# power_supply.net
KiCad netlist of a schematic drawn in Altium Designer
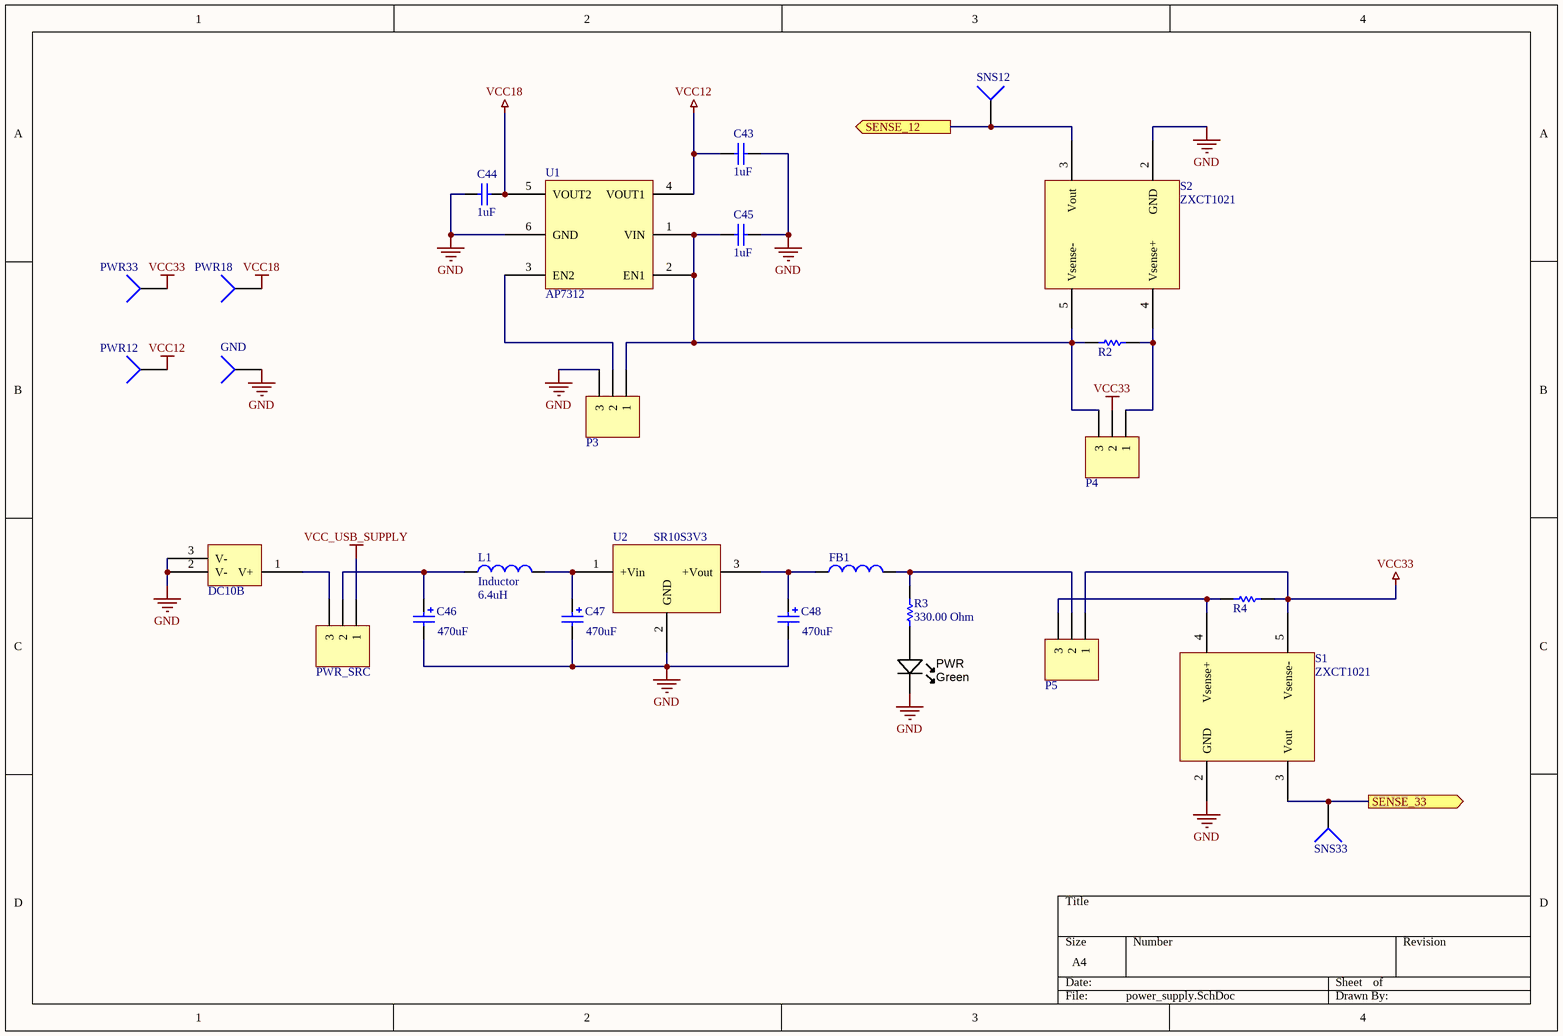
[diagram p0: power_supply.SchDoc]

(export (version "E")
  (design (tool "Eeschema 10.0.6"))
  (components
    (comp (ref "C43")
      (value "1uF")
      (footprint "CAPC0805(2012)100_N")
      (description "CAP 1uF 16V ±10% 0805 (2012 Metric) Thickness 1mm SMD")
      (fields (field (name "TOLERANCE") "±10%"))
      (libsource (lib "Altium Content Vault") (part "CMP-1036-04747-1"))
    )
    (comp (ref "C44")
      (value "1uF")
      (footprint "CAPC0805(2012)100_N")
      (description "CAP 1uF 16V ±10% 0805 (2012 Metric) Thickness 1mm SMD")
      (fields (field (name "TOLERANCE") "±10%"))
      (libsource (lib "Altium Content Vault") (part "CMP-1036-04747-1"))
    )
    (comp (ref "C45")
      (value "1uF")
      (footprint "CAPC0805(2012)100_N")
      (description "CAP 1uF 16V ±10% 0805 (2012 Metric) Thickness 1mm SMD")
      (fields (field (name "TOLERANCE") "±10%"))
      (libsource (lib "Altium Content Vault") (part "CMP-1036-04747-1"))
    )
    (comp (ref "C46")
      (value "470uF")
      (footprint "CAP470uF")
      (description "Polarized Capacitor (Axial)")
      (fields (field (name "Comment") "Cap Pol2") (field (name "PUBLISHER") "Altium Limited"))
      (libsource (lib "Miscellaneous Devices") (part "Cap Pol2"))
    )
    (comp (ref "C47")
      (value "470uF")
      (footprint "CAP470uF")
      (description "Polarized Capacitor (Axial)")
      (fields (field (name "Comment") "Cap Pol2") (field (name "PUBLISHER") "Altium Limited"))
      (libsource (lib "Miscellaneous Devices") (part "Cap Pol2"))
    )
    (comp (ref "C48")
      (value "470uF")
      (footprint "CAP470uF")
      (description "Polarized Capacitor (Axial)")
      (fields (field (name "Comment") "Cap Pol2") (field (name "PUBLISHER") "Altium Limited"))
      (libsource (lib "Miscellaneous Devices") (part "Cap Pol2"))
    )
    (comp (ref "FB1")
      (value "Inductor")
      (footprint "INDC3216")
      (fields (field (name "PUBLISHER") "Altium Limited"))
      (libsource (lib "Miscellaneous Devices") (part "Inductor"))
    )
    (comp (ref "GND")
      (value "Socket")
      (footprint "PIN1")
      (fields (field (name "PUBLISHER") "Altium Limited"))
      (libsource (lib "Miscellaneous Connectors") (part "Socket"))
    )
    (comp (ref "L1")
      (value "Inductor")
      (footprint "Coil DRA74-6R8-R")
      (fields (field (name "ALTIUM_VALUE") "6.4uH") (field (name "PUBLISHER") "Altium Limited"))
      (libsource (lib "Miscellaneous Devices") (part "Inductor"))
    )
    (comp (ref "P3")
      (value "Header 3")
      (footprint "HDR1X3")
      (description "Header, 3-Pin")
      (fields (field (name "PUBLISHER") "Altium Limited"))
      (libsource (lib "Miscellaneous Connectors") (part "Header 3"))
    )
    (comp (ref "P4")
      (value "Header 3")
      (footprint "HDR1X3")
      (description "Header, 3-Pin")
      (fields (field (name "PUBLISHER") "Altium Limited"))
      (libsource (lib "Miscellaneous Connectors") (part "Header 3"))
    )
    (comp (ref "P5")
      (value "Header 3")
      (footprint "HDR1X3")
      (description "Header, 3-Pin")
      (fields (field (name "PUBLISHER") "Altium Limited"))
      (libsource (lib "Miscellaneous Connectors") (part "Header 3"))
    )
    (comp (ref "PWR")
      (value "Green")
      (footprint "LED-0805-K")
      (description "LED, 0805 SMD, Green")
      (libsource (lib "PBL - Light Sources") (part "LED_SMD_Green_0805"))
    )
    (comp (ref "PWR12")
      (value "Socket")
      (footprint "PIN1")
      (fields (field (name "PUBLISHER") "Altium Limited"))
      (libsource (lib "Miscellaneous Connectors") (part "Socket"))
    )
    (comp (ref "PWR18")
      (value "Socket")
      (footprint "PIN1")
      (fields (field (name "PUBLISHER") "Altium Limited"))
      (libsource (lib "Miscellaneous Connectors") (part "Socket"))
    )
    (comp (ref "PWR33")
      (value "Socket")
      (footprint "PIN1")
      (fields (field (name "PUBLISHER") "Altium Limited"))
      (libsource (lib "Miscellaneous Connectors") (part "Socket"))
    )
    (comp (ref "PWRCON")
      (value "DC10B")
      (footprint "DC-10B")
      (libsource (lib "PowerConnector") (part "DC10B"))
    )
    (comp (ref "PWR_SRC")
      (value "Header 3")
      (footprint "HDR1X3")
      (description "Header, 3-Pin")
      (fields (field (name "PUBLISHER") "Altium Limited"))
      (libsource (lib "Miscellaneous Connectors") (part "Header 3"))
    )
    (comp (ref "R2")
      (value "10R 5% 0805(2012)")
      (footprint "RESC0805(2012)_L")
      (description "10R 0.125W 5% 0805 (2012 Metric)  SMD")
      (fields (field (name "POWER") "0.125 W") (field (name "TOLERANCE") "5 %"))
      (libsource (lib "Altium Content Vault") (part "RES"))
    )
    (comp (ref "R3")
      (value "330.00 Ohm")
      (footprint "RESC0805(2012)_M")
      (description "330R 0.125W 1% 0805 (2012 Metric)  SMD")
      (fields (field (name "POWER") "0.125 W") (field (name "TOLERANCE") "1 %"))
      (libsource (lib "Altium Content Vault") (part "CMP-1013-00454-1"))
    )
    (comp (ref "R4")
      (value "10R 5% 0805(2012)")
      (footprint "RESC0805(2012)_L")
      (description "10R 0.125W 5% 0805 (2012 Metric)  SMD")
      (fields (field (name "POWER") "0.125 W") (field (name "TOLERANCE") "5 %"))
      (libsource (lib "Altium Content Vault") (part "RES"))
    )
    (comp (ref "S1")
      (value "ZXCT1021")
      (footprint "SOT95P270X145-5N")
      (libsource (lib "") (part "ZXCT1021_1"))
    )
    (comp (ref "S2")
      (value "ZXCT1021")
      (footprint "SOT95P270X145-5N")
      (libsource (lib "SR10S3V3_Schematic") (part "ZXCT1021"))
    )
    (comp (ref "SNS12")
      (value "Socket")
      (footprint "PIN1")
      (fields (field (name "PUBLISHER") "Altium Limited"))
      (libsource (lib "Miscellaneous Connectors") (part "Socket"))
    )
    (comp (ref "SNS33")
      (value "Socket")
      (footprint "PIN1")
      (fields (field (name "PUBLISHER") "Altium Limited"))
      (libsource (lib "Miscellaneous Connectors") (part "Socket"))
    )
    (comp (ref "U1")
      (value "AP7312")
      (footprint "SOT95P285X145-6N")
      (libsource (lib "SR10S3V3_Schematic") (part "AP7312"))
    )
    (comp (ref "U2")
      (value "SR10S3V3")
      (footprint "SR10S3V3_Footprint")
      (libsource (lib "Schematic Components") (part "SR10S3V3"))
    )
  )
  (nets
    (net (code "1") (name "/SENSE_12") (class "Default")
      (node (ref "S2") (pin "3") (pinfunction "Vout_3") (pintype "passive"))
      (node (ref "SNS12") (pin "1") (pinfunction "1_1") (pintype "passive"))
    )
    (net (code "2") (name "/SENSE_33") (class "Default")
      (node (ref "S1") (pin "3") (pinfunction "Vout_3") (pintype "passive"))
      (node (ref "SNS33") (pin "1") (pinfunction "1_1") (pintype "passive"))
    )
    (net (code "3") (name "GND") (class "Default")
      (node (ref "C43") (pin "2") (pinfunction "2_2") (pintype "passive"))
      (node (ref "C44") (pin "1") (pinfunction "1_1") (pintype "passive"))
      (node (ref "C45") (pin "2") (pinfunction "2_2") (pintype "passive"))
      (node (ref "C46") (pin "2") (pinfunction "2_2") (pintype "passive"))
      (node (ref "C47") (pin "2") (pinfunction "2_2") (pintype "passive"))
      (node (ref "C48") (pin "2") (pinfunction "2_2") (pintype "passive"))
      (node (ref "GND") (pin "1") (pinfunction "1_1") (pintype "passive"))
      (node (ref "P3") (pin "3") (pinfunction "3_3") (pintype "passive"))
      (node (ref "PWR") (pin "K") (pinfunction "K_K") (pintype "passive"))
      (node (ref "PWRCON") (pin "2") (pinfunction "V-_2") (pintype "passive"))
      (node (ref "PWRCON") (pin "3") (pinfunction "V-_3") (pintype "passive"))
      (node (ref "S1") (pin "2") (pinfunction "GND_2") (pintype "passive"))
      (node (ref "S2") (pin "2") (pinfunction "GND_2") (pintype "passive"))
      (node (ref "U1") (pin "6") (pinfunction "GND_6") (pintype "passive"))
      (node (ref "U2") (pin "2") (pinfunction "GND_2") (pintype "passive"))
    )
    (net (code "4") (name "Net-(C46-Pad1)") (class "Default")
      (node (ref "C46") (pin "1") (pinfunction "1_1") (pintype "passive"))
      (node (ref "L1") (pin "1") (pinfunction "1_1") (pintype "passive"))
      (node (ref "PWR_SRC") (pin "2") (pinfunction "2_2") (pintype "passive"))
    )
    (net (code "5") (name "Net-(FB1-Pad2)") (class "Default")
      (node (ref "FB1") (pin "2") (pinfunction "2_2") (pintype "passive"))
      (node (ref "P5") (pin "2") (pinfunction "2_2") (pintype "passive"))
      (node (ref "R3") (pin "2") (pinfunction "2_2") (pintype "passive"))
    )
    (net (code "6") (name "Net-(PWR-PadA)") (class "Default")
      (node (ref "PWR") (pin "A") (pinfunction "A_A") (pintype "passive"))
      (node (ref "R3") (pin "1") (pinfunction "1_1") (pintype "passive"))
    )
    (net (code "7") (name "Net-(PWRCON-V+)") (class "Default")
      (node (ref "PWRCON") (pin "1") (pinfunction "V+_1") (pintype "passive"))
      (node (ref "PWR_SRC") (pin "3") (pinfunction "3_3") (pintype "passive"))
    )
    (net (code "8") (name "Net-(S1-Vsense+)") (class "Default")
      (node (ref "P5") (pin "3") (pinfunction "3_3") (pintype "passive"))
      (node (ref "R4") (pin "1") (pinfunction "1_1") (pintype "passive"))
      (node (ref "S1") (pin "4") (pinfunction "Vsense+_4") (pintype "passive"))
    )
    (net (code "9") (name "Net-(S2-Vsense+)") (class "Default")
      (node (ref "P4") (pin "1") (pinfunction "1_1") (pintype "passive"))
      (node (ref "R2") (pin "2") (pinfunction "2_2") (pintype "passive"))
      (node (ref "S2") (pin "4") (pinfunction "Vsense+_4") (pintype "passive"))
    )
    (net (code "10") (name "Net-(S2-Vsense-)") (class "Default")
      (node (ref "C45") (pin "1") (pinfunction "1_1") (pintype "passive"))
      (node (ref "P3") (pin "1") (pinfunction "1_1") (pintype "passive"))
      (node (ref "P4") (pin "3") (pinfunction "3_3") (pintype "passive"))
      (node (ref "R2") (pin "1") (pinfunction "1_1") (pintype "passive"))
      (node (ref "S2") (pin "5") (pinfunction "Vsense-_5") (pintype "passive"))
      (node (ref "U1") (pin "1") (pinfunction "VIN_1") (pintype "passive"))
      (node (ref "U1") (pin "2") (pinfunction "EN1_2") (pintype "passive"))
    )
    (net (code "11") (name "Net-(U1-EN2)") (class "Default")
      (node (ref "P3") (pin "2") (pinfunction "2_2") (pintype "passive"))
      (node (ref "U1") (pin "3") (pinfunction "EN2_3") (pintype "passive"))
    )
    (net (code "12") (name "Net-(U2-+Vin)") (class "Default")
      (node (ref "C47") (pin "1") (pinfunction "1_1") (pintype "passive"))
      (node (ref "L1") (pin "2") (pinfunction "2_2") (pintype "passive"))
      (node (ref "U2") (pin "1") (pinfunction "+Vin_1") (pintype "passive"))
    )
    (net (code "13") (name "Net-(U2-+Vout)") (class "Default")
      (node (ref "C48") (pin "1") (pinfunction "1_1") (pintype "passive"))
      (node (ref "FB1") (pin "1") (pinfunction "1_1") (pintype "passive"))
      (node (ref "U2") (pin "3") (pinfunction "+Vout_3") (pintype "passive"))
    )
    (net (code "14") (name "VCC12") (class "Default")
      (node (ref "C43") (pin "1") (pinfunction "1_1") (pintype "passive"))
      (node (ref "PWR12") (pin "1") (pinfunction "1_1") (pintype "passive"))
      (node (ref "U1") (pin "4") (pinfunction "VOUT1_4") (pintype "passive"))
    )
    (net (code "15") (name "VCC18") (class "Default")
      (node (ref "C44") (pin "2") (pinfunction "2_2") (pintype "passive"))
      (node (ref "PWR18") (pin "1") (pinfunction "1_1") (pintype "passive"))
      (node (ref "U1") (pin "5") (pinfunction "VOUT2_5") (pintype "passive"))
    )
    (net (code "16") (name "VCC33") (class "Default")
      (node (ref "P4") (pin "2") (pinfunction "2_2") (pintype "passive"))
      (node (ref "P5") (pin "1") (pinfunction "1_1") (pintype "passive"))
      (node (ref "PWR33") (pin "1") (pinfunction "1_1") (pintype "passive"))
      (node (ref "R4") (pin "2") (pinfunction "2_2") (pintype "passive"))
      (node (ref "S1") (pin "5") (pinfunction "Vsense-_5") (pintype "passive"))
    )
    (net (code "17") (name "VCC_USB_SUPPLY") (class "Default")
      (node (ref "PWR_SRC") (pin "1") (pinfunction "1_1") (pintype "passive"))
    )
  )
)
